# Power_Switch.net
KiCad netlist of a schematic drawn in EAGLE
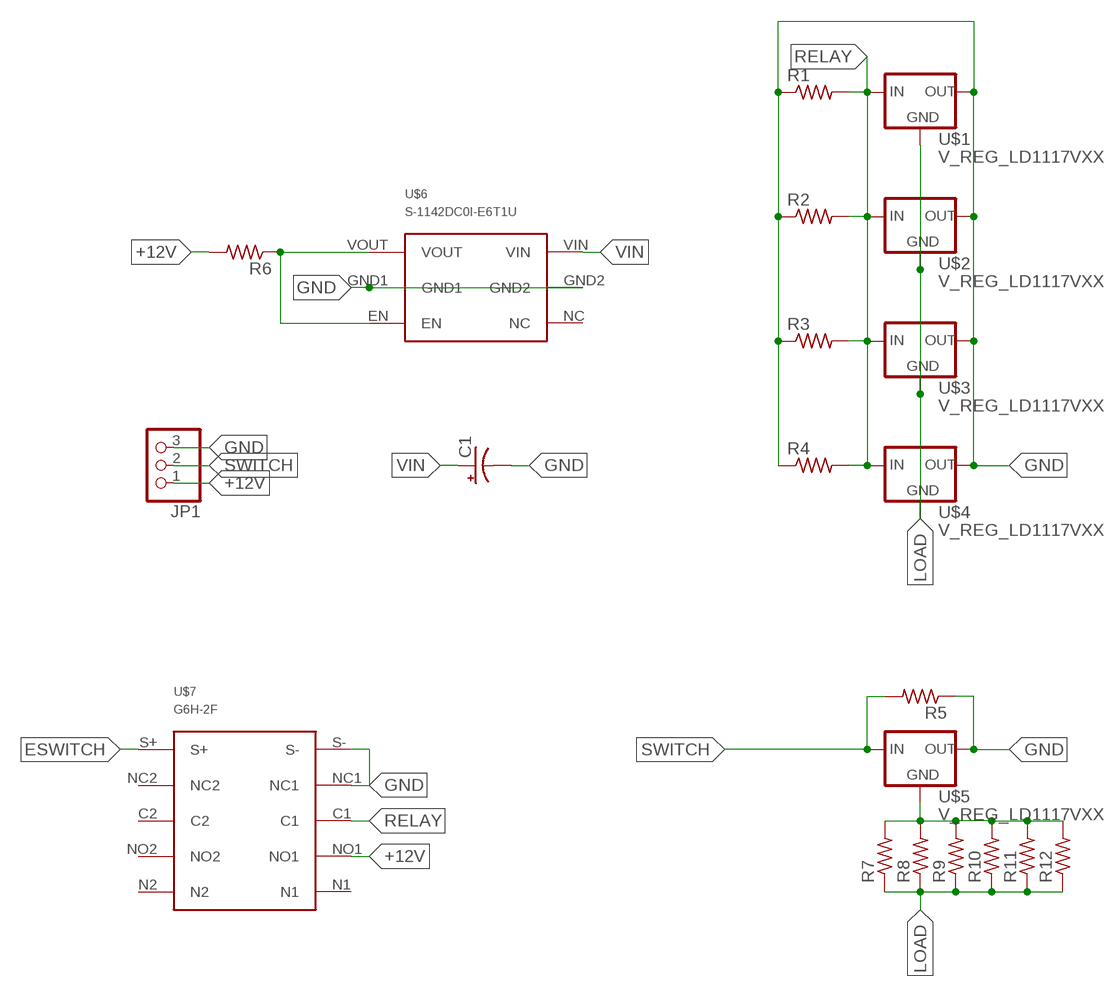
[diagram p0: schematic, sheet 1]

(export (version "E")
  (design (tool "Eeschema 10.0.6"))
  (components
    (comp (ref "C1")
      (value "CPOL-US153CLV-0810")
      (footprint "eagle-import:153CLV-0810")
      (libsource (lib "eagle-import") (part "CPOL-US153CLV-0810"))
    )
    (comp (ref "JP1")
      (value "PINHD-1X3")
      (footprint "eagle-import:1X03")
      (libsource (lib "eagle-import") (part "PINHD-1X3"))
    )
    (comp (ref "R1")
      (value "R-US_R0805")
      (footprint "eagle-import:R0805")
      (libsource (lib "eagle-import") (part "R-US_R0805"))
    )
    (comp (ref "R2")
      (value "R-US_R0805")
      (footprint "eagle-import:R0805")
      (libsource (lib "eagle-import") (part "R-US_R0805"))
    )
    (comp (ref "R3")
      (value "R-US_R0805")
      (footprint "eagle-import:R0805")
      (libsource (lib "eagle-import") (part "R-US_R0805"))
    )
    (comp (ref "R4")
      (value "R-US_R0805")
      (footprint "eagle-import:R0805")
      (libsource (lib "eagle-import") (part "R-US_R0805"))
    )
    (comp (ref "R5")
      (value "R-US_R0805")
      (footprint "eagle-import:R0805")
      (libsource (lib "eagle-import") (part "R-US_R0805"))
    )
    (comp (ref "R6")
      (value "R-US_R0805")
      (footprint "eagle-import:R0805")
      (libsource (lib "eagle-import") (part "R-US_R0805"))
    )
    (comp (ref "R7")
      (value "R-US_R0805")
      (footprint "eagle-import:R0805")
      (libsource (lib "eagle-import") (part "R-US_R0805"))
    )
    (comp (ref "R8")
      (value "R-US_R0805")
      (footprint "eagle-import:R0805")
      (libsource (lib "eagle-import") (part "R-US_R0805"))
    )
    (comp (ref "R9")
      (value "R-US_R0805")
      (footprint "eagle-import:R0805")
      (libsource (lib "eagle-import") (part "R-US_R0805"))
    )
    (comp (ref "R10")
      (value "R-US_R0805")
      (footprint "eagle-import:R0805")
      (libsource (lib "eagle-import") (part "R-US_R0805"))
    )
    (comp (ref "R11")
      (value "R-US_R0805")
      (footprint "eagle-import:R0805")
      (libsource (lib "eagle-import") (part "R-US_R0805"))
    )
    (comp (ref "R12")
      (value "R-US_R0805")
      (footprint "eagle-import:R0805")
      (libsource (lib "eagle-import") (part "R-US_R0805"))
    )
    (comp (ref "U$1")
      (value "V_REG_LD1117VXX")
      (footprint "eagle-import:78XXL")
      (libsource (lib "eagle-import") (part "V_REG_LD1117VXX"))
    )
    (comp (ref "U$2")
      (value "V_REG_LD1117VXX")
      (footprint "eagle-import:78XXL")
      (libsource (lib "eagle-import") (part "V_REG_LD1117VXX"))
    )
    (comp (ref "U$3")
      (value "V_REG_LD1117VXX")
      (footprint "eagle-import:78XXL")
      (libsource (lib "eagle-import") (part "V_REG_LD1117VXX"))
    )
    (comp (ref "U$4")
      (value "V_REG_LD1117VXX")
      (footprint "eagle-import:78XXL")
      (libsource (lib "eagle-import") (part "V_REG_LD1117VXX"))
    )
    (comp (ref "U$5")
      (value "V_REG_LD1117VXX")
      (footprint "eagle-import:78XXL")
      (libsource (lib "eagle-import") (part "V_REG_LD1117VXX"))
    )
    (comp (ref "U$6")
      (value "S-1142DC0I-E6T1U")
      (footprint "eagle-import:S-1142DC0I-E6T1U")
      (libsource (lib "eagle-import") (part "S-1142DC0I-E6T1U"))
    )
    (comp (ref "U$7")
      (value "G6H-2F")
      (footprint "eagle-import:G6H-2F")
      (libsource (lib "eagle-import") (part "G6H-2F"))
    )
  )
  (nets
    (net (code "1") (name "+12V") (class "Default")
      (node (ref "JP1") (pin "1") (pinfunction "1_1") (pintype "passive"))
      (node (ref "R6") (pin "2") (pinfunction "2_2") (pintype "passive"))
      (node (ref "U$7") (pin "NO1") (pinfunction "NO1_NO1") (pintype "bidirectional"))
    )
    (net (code "2") (name "ESWITCH") (class "Default")
      (node (ref "U$7") (pin "S+") (pinfunction "S+_S+") (pintype "bidirectional"))
    )
    (net (code "3") (name "GND") (class "Default")
      (node (ref "C1") (pin "-") (pinfunction "-_-") (pintype "passive"))
      (node (ref "JP1") (pin "3") (pinfunction "3_3") (pintype "passive"))
      (node (ref "R1") (pin "1") (pinfunction "1_1") (pintype "passive"))
      (node (ref "R2") (pin "1") (pinfunction "1_1") (pintype "passive"))
      (node (ref "R3") (pin "1") (pinfunction "1_1") (pintype "passive"))
      (node (ref "R4") (pin "1") (pinfunction "1_1") (pintype "passive"))
      (node (ref "R5") (pin "1") (pinfunction "1_1") (pintype "passive"))
      (node (ref "U$1") (pin "OUT") (pinfunction "OUT_OUT") (pintype "passive"))
      (node (ref "U$2") (pin "OUT") (pinfunction "OUT_OUT") (pintype "passive"))
      (node (ref "U$3") (pin "OUT") (pinfunction "OUT_OUT") (pintype "passive"))
      (node (ref "U$4") (pin "OUT") (pinfunction "OUT_OUT") (pintype "passive"))
      (node (ref "U$5") (pin "OUT") (pinfunction "OUT_OUT") (pintype "passive"))
      (node (ref "U$6") (pin "GND1") (pinfunction "GND1_GND1") (pintype "bidirectional"))
      (node (ref "U$6") (pin "GND2") (pinfunction "GND2_GND2") (pintype "bidirectional"))
      (node (ref "U$7") (pin "NC1") (pinfunction "NC1_NC1") (pintype "bidirectional"))
      (node (ref "U$7") (pin "S-") (pinfunction "S-_S-") (pintype "bidirectional"))
    )
    (net (code "4") (name "LOAD") (class "Default")
      (node (ref "R10") (pin "1") (pinfunction "1_1") (pintype "passive"))
      (node (ref "R11") (pin "1") (pinfunction "1_1") (pintype "passive"))
      (node (ref "R12") (pin "1") (pinfunction "1_1") (pintype "passive"))
      (node (ref "R7") (pin "1") (pinfunction "1_1") (pintype "passive"))
      (node (ref "R8") (pin "1") (pinfunction "1_1") (pintype "passive"))
      (node (ref "R9") (pin "1") (pinfunction "1_1") (pintype "passive"))
      (node (ref "U$1") (pin "GND") (pinfunction "GND_GND") (pintype "input"))
      (node (ref "U$2") (pin "GND") (pinfunction "GND_GND") (pintype "input"))
      (node (ref "U$3") (pin "GND") (pinfunction "GND_GND") (pintype "input"))
      (node (ref "U$4") (pin "GND") (pinfunction "GND_GND") (pintype "input"))
    )
    (net (code "5") (name "Net-(R6-Pad1)") (class "Default")
      (node (ref "R6") (pin "1") (pinfunction "1_1") (pintype "passive"))
      (node (ref "U$6") (pin "EN") (pinfunction "EN_EN") (pintype "bidirectional"))
      (node (ref "U$6") (pin "VOUT") (pinfunction "VOUT_VOUT") (pintype "bidirectional"))
    )
    (net (code "6") (name "Net-(R10-Pad2)") (class "Default")
      (node (ref "R10") (pin "2") (pinfunction "2_2") (pintype "passive"))
      (node (ref "R11") (pin "2") (pinfunction "2_2") (pintype "passive"))
      (node (ref "R12") (pin "2") (pinfunction "2_2") (pintype "passive"))
      (node (ref "R7") (pin "2") (pinfunction "2_2") (pintype "passive"))
      (node (ref "R8") (pin "2") (pinfunction "2_2") (pintype "passive"))
      (node (ref "R9") (pin "2") (pinfunction "2_2") (pintype "passive"))
      (node (ref "U$5") (pin "GND") (pinfunction "GND_GND") (pintype "input"))
    )
    (net (code "7") (name "RELAY") (class "Default")
      (node (ref "R1") (pin "2") (pinfunction "2_2") (pintype "passive"))
      (node (ref "R2") (pin "2") (pinfunction "2_2") (pintype "passive"))
      (node (ref "R3") (pin "2") (pinfunction "2_2") (pintype "passive"))
      (node (ref "R4") (pin "2") (pinfunction "2_2") (pintype "passive"))
      (node (ref "U$1") (pin "IN") (pinfunction "IN_IN") (pintype "input"))
      (node (ref "U$2") (pin "IN") (pinfunction "IN_IN") (pintype "input"))
      (node (ref "U$3") (pin "IN") (pinfunction "IN_IN") (pintype "input"))
      (node (ref "U$4") (pin "IN") (pinfunction "IN_IN") (pintype "input"))
      (node (ref "U$7") (pin "C1") (pinfunction "C1_C1") (pintype "bidirectional"))
    )
    (net (code "8") (name "SWITCH") (class "Default")
      (node (ref "JP1") (pin "2") (pinfunction "2_2") (pintype "passive"))
      (node (ref "R5") (pin "2") (pinfunction "2_2") (pintype "passive"))
      (node (ref "U$5") (pin "IN") (pinfunction "IN_IN") (pintype "input"))
    )
    (net (code "9") (name "VIN") (class "Default")
      (node (ref "C1") (pin "+") (pinfunction "+_+") (pintype "passive"))
      (node (ref "U$6") (pin "VIN") (pinfunction "VIN_VIN") (pintype "bidirectional"))
    )
    (net (code "10") (name "unconnected-(U$6-PadNC)") (class "Default")
      (node (ref "U$6") (pin "NC") (pinfunction "NC_NC") (pintype "bidirectional"))
    )
    (net (code "11") (name "unconnected-(U$7-PadC2)") (class "Default")
      (node (ref "U$7") (pin "C2") (pinfunction "C2_C2") (pintype "bidirectional"))
    )
    (net (code "12") (name "unconnected-(U$7-PadN1)") (class "Default")
      (node (ref "U$7") (pin "N1") (pinfunction "N1_N1") (pintype "bidirectional"))
    )
    (net (code "13") (name "unconnected-(U$7-PadN2)") (class "Default")
      (node (ref "U$7") (pin "N2") (pinfunction "N2_N2") (pintype "bidirectional"))
    )
    (net (code "14") (name "unconnected-(U$7-PadNC2)") (class "Default")
      (node (ref "U$7") (pin "NC2") (pinfunction "NC2_NC2") (pintype "bidirectional"))
    )
    (net (code "15") (name "unconnected-(U$7-PadNO2)") (class "Default")
      (node (ref "U$7") (pin "NO2") (pinfunction "NO2_NO2") (pintype "bidirectional"))
    )
  )
)
